# lock-shield.net
KiCad netlist of a schematic drawn in EAGLE
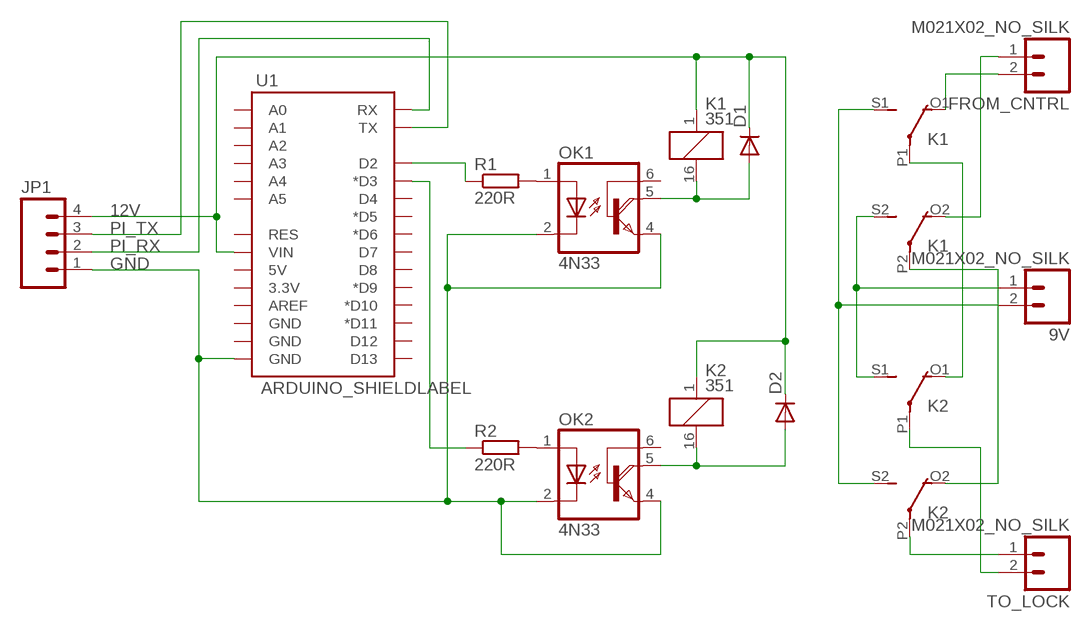
[diagram p0: schematic, sheet 1]

(export (version "E")
  (design (tool "Eeschema 10.0.6"))
  (components
    (comp (ref "9V")
      (value "M021X02_NO_SILK")
      (footprint "eagle-import:1X02_NO_SILK")
      (libsource (lib "eagle-import") (part "M021X02_NO_SILK"))
    )
    (comp (ref "D1")
      (value "DIODE1N4148")
      (footprint "eagle-import:DIODE-1N4148")
      (libsource (lib "eagle-import") (part "DIODE1N4148"))
    )
    (comp (ref "D2")
      (value "DIODE1N4148")
      (footprint "eagle-import:DIODE-1N4148")
      (libsource (lib "eagle-import") (part "DIODE1N4148"))
    )
    (comp (ref "FROM_CNTRL")
      (value "M021X02_NO_SILK")
      (footprint "eagle-import:1X02_NO_SILK")
      (libsource (lib "eagle-import") (part "M021X02_NO_SILK"))
    )
    (comp (ref "JP1")
      (value "M041X04_NO_SILK")
      (footprint "eagle-import:1X04_NO_SILK")
      (libsource (lib "eagle-import") (part "M041X04_NO_SILK"))
    )
    (comp (ref "K1")
      (value "351")
      (footprint "eagle-import:351")
      (libsource (lib "eagle-import") (part "351"))
    )
    (comp (ref "K2")
      (value "351")
      (footprint "eagle-import:351")
      (libsource (lib "eagle-import") (part "351"))
    )
    (comp (ref "OK1")
      (value "4N33")
      (footprint "eagle-import:DIL06")
      (fields (field (name "MF") "VISHAY/TELEFUNKEN"))
      (libsource (lib "eagle-import") (part "4N33"))
    )
    (comp (ref "OK2")
      (value "4N33")
      (footprint "eagle-import:DIL06")
      (fields (field (name "MF") "VISHAY/TELEFUNKEN"))
      (libsource (lib "eagle-import") (part "4N33"))
    )
    (comp (ref "R1")
      (value "220R")
      (footprint "eagle-import:0309_10")
      (libsource (lib "eagle-import") (part "R-EU_0309/10"))
    )
    (comp (ref "R2")
      (value "220R")
      (footprint "eagle-import:0309_10")
      (libsource (lib "eagle-import") (part "R-EU_0309/10"))
    )
    (comp (ref "TO_LOCK")
      (value "M021X02_NO_SILK")
      (footprint "eagle-import:1X02_NO_SILK")
      (libsource (lib "eagle-import") (part "M021X02_NO_SILK"))
    )
    (comp (ref "U1")
      (value "ARDUINO_SHIELDLABEL")
      (footprint "eagle-import:DUEMILANOVE_SHIELD")
      (libsource (lib "eagle-import") (part "ARDUINO_SHIELDLABEL"))
    )
  )
  (nets
    (net (code "1") (name "/12V") (class "Default")
      (node (ref "D1") (pin "C") (pinfunction "C_C") (pintype "passive"))
      (node (ref "D2") (pin "C") (pinfunction "C_C") (pintype "passive"))
      (node (ref "JP1") (pin "4") (pinfunction "4_4") (pintype "passive"))
      (node (ref "K1") (pin "1") (pinfunction "1_1") (pintype "passive"))
      (node (ref "K2") (pin "1") (pinfunction "1_1") (pintype "passive"))
      (node (ref "U1") (pin "VIN") (pinfunction "VIN_VIN") (pintype "bidirectional"))
    )
    (net (code "2") (name "/GND") (class "Default")
      (node (ref "JP1") (pin "1") (pinfunction "1_1") (pintype "passive"))
      (node (ref "OK1") (pin "2") (pinfunction "C_2") (pintype "passive"))
      (node (ref "OK1") (pin "4") (pinfunction "E_4") (pintype "passive"))
      (node (ref "OK2") (pin "2") (pinfunction "C_2") (pintype "passive"))
      (node (ref "OK2") (pin "4") (pinfunction "E_4") (pintype "passive"))
      (node (ref "U1") (pin "GND@0") (pinfunction "GND_GND@0") (pintype "bidirectional"))
    )
    (net (code "3") (name "/PI_RX") (class "Default")
      (node (ref "JP1") (pin "2") (pinfunction "2_2") (pintype "passive"))
      (node (ref "U1") (pin "RX") (pinfunction "RX_RX") (pintype "bidirectional"))
    )
    (net (code "4") (name "/PI_TX") (class "Default")
      (node (ref "JP1") (pin "3") (pinfunction "3_3") (pintype "passive"))
      (node (ref "U1") (pin "TX") (pinfunction "TX_TX") (pintype "bidirectional"))
    )
    (net (code "5") (name "Net-(K1A-2)") (class "Default")
      (node (ref "D1") (pin "A") (pinfunction "A_A") (pintype "passive"))
      (node (ref "K1") (pin "16") (pinfunction "2_16") (pintype "passive"))
      (node (ref "OK1") (pin "5") (pinfunction "COL_5") (pintype "passive"))
    )
    (net (code "6") (name "Net-(K1B-O)") (class "Default")
      (node (ref "FROM_CNTRL") (pin "2") (pinfunction "2_2") (pintype "passive"))
      (node (ref "K1") (pin "O1") (pinfunction "O_O1") (pintype "passive"))
    )
    (net (code "7") (name "Net-(K1B-P)") (class "Default")
      (node (ref "K1") (pin "P1") (pinfunction "P_P1") (pintype "passive"))
      (node (ref "K2") (pin "O1") (pinfunction "O_O1") (pintype "passive"))
    )
    (net (code "8") (name "Net-(K1B-S)") (class "Default")
      (node (ref "9V") (pin "2") (pinfunction "2_2") (pintype "passive"))
      (node (ref "K1") (pin "S1") (pinfunction "S_S1") (pintype "passive"))
      (node (ref "K2") (pin "S2") (pinfunction "S_S2") (pintype "passive"))
    )
    (net (code "9") (name "Net-(K1C-O)") (class "Default")
      (node (ref "FROM_CNTRL") (pin "1") (pinfunction "1_1") (pintype "passive"))
      (node (ref "K1") (pin "O2") (pinfunction "O_O2") (pintype "passive"))
    )
    (net (code "10") (name "Net-(K1C-P)") (class "Default")
      (node (ref "K1") (pin "P2") (pinfunction "P_P2") (pintype "passive"))
      (node (ref "K2") (pin "O2") (pinfunction "O_O2") (pintype "passive"))
    )
    (net (code "11") (name "Net-(K1C-S)") (class "Default")
      (node (ref "9V") (pin "1") (pinfunction "1_1") (pintype "passive"))
      (node (ref "K1") (pin "S2") (pinfunction "S_S2") (pintype "passive"))
      (node (ref "K2") (pin "S1") (pinfunction "S_S1") (pintype "passive"))
    )
    (net (code "12") (name "Net-(K2A-2)") (class "Default")
      (node (ref "D2") (pin "A") (pinfunction "A_A") (pintype "passive"))
      (node (ref "K2") (pin "16") (pinfunction "2_16") (pintype "passive"))
      (node (ref "OK2") (pin "5") (pinfunction "COL_5") (pintype "passive"))
    )
    (net (code "13") (name "Net-(K2B-P)") (class "Default")
      (node (ref "K2") (pin "P1") (pinfunction "P_P1") (pintype "passive"))
      (node (ref "TO_LOCK") (pin "2") (pinfunction "2_2") (pintype "passive"))
    )
    (net (code "14") (name "Net-(K2C-P)") (class "Default")
      (node (ref "K2") (pin "P2") (pinfunction "P_P2") (pintype "passive"))
      (node (ref "TO_LOCK") (pin "1") (pinfunction "1_1") (pintype "passive"))
    )
    (net (code "15") (name "Net-(OK1-A)") (class "Default")
      (node (ref "OK1") (pin "1") (pinfunction "A_1") (pintype "passive"))
      (node (ref "R1") (pin "2") (pinfunction "2_2") (pintype "passive"))
    )
    (net (code "16") (name "Net-(OK2-A)") (class "Default")
      (node (ref "OK2") (pin "1") (pinfunction "A_1") (pintype "passive"))
      (node (ref "R2") (pin "2") (pinfunction "2_2") (pintype "passive"))
    )
    (net (code "17") (name "Net-(R1-Pad1)") (class "Default")
      (node (ref "R1") (pin "1") (pinfunction "1_1") (pintype "passive"))
      (node (ref "U1") (pin "D2") (pinfunction "D2_D2") (pintype "bidirectional"))
    )
    (net (code "18") (name "Net-(U1-*D3)") (class "Default")
      (node (ref "R2") (pin "1") (pinfunction "1_1") (pintype "passive"))
      (node (ref "U1") (pin "D3") (pinfunction "*D3_D3") (pintype "bidirectional"))
    )
    (net (code "19") (name "unconnected-(OK1-B-Pad6)") (class "Default")
      (node (ref "OK1") (pin "6") (pinfunction "B_6") (pintype "passive"))
    )
    (net (code "20") (name "unconnected-(OK2-B-Pad6)") (class "Default")
      (node (ref "OK2") (pin "6") (pinfunction "B_6") (pintype "passive"))
    )
    (net (code "21") (name "unconnected-(U1-*D5-PadD5)") (class "Default")
      (node (ref "U1") (pin "D5") (pinfunction "*D5_D5") (pintype "bidirectional"))
    )
    (net (code "22") (name "unconnected-(U1-*D6-PadD6)") (class "Default")
      (node (ref "U1") (pin "D6") (pinfunction "*D6_D6") (pintype "bidirectional"))
    )
    (net (code "23") (name "unconnected-(U1-*D9-PadD9)") (class "Default")
      (node (ref "U1") (pin "D9") (pinfunction "*D9_D9") (pintype "bidirectional"))
    )
    (net (code "24") (name "unconnected-(U1-*D10-PadD10)") (class "Default")
      (node (ref "U1") (pin "D10") (pinfunction "*D10_D10") (pintype "bidirectional"))
    )
    (net (code "25") (name "unconnected-(U1-*D11-PadD11)") (class "Default")
      (node (ref "U1") (pin "D11") (pinfunction "*D11_D11") (pintype "bidirectional"))
    )
    (net (code "26") (name "unconnected-(U1-GND-PadGND@1)") (class "Default")
      (node (ref "U1") (pin "GND@1") (pinfunction "GND_GND@1") (pintype "bidirectional"))
    )
    (net (code "27") (name "unconnected-(U1-GND-PadGND@2)") (class "Default")
      (node (ref "U1") (pin "GND@2") (pinfunction "GND_GND@2") (pintype "bidirectional"))
    )
    (net (code "28") (name "unconnected-(U1-Pad3.3V)") (class "Default")
      (node (ref "U1") (pin "3.3V") (pinfunction "3.3V_3.3V") (pintype "bidirectional"))
    )
    (net (code "29") (name "unconnected-(U1-Pad5V)") (class "Default")
      (node (ref "U1") (pin "5V") (pinfunction "5V_5V") (pintype "bidirectional"))
    )
    (net (code "30") (name "unconnected-(U1-PadA0)") (class "Default")
      (node (ref "U1") (pin "A0") (pinfunction "A0_A0") (pintype "bidirectional"))
    )
    (net (code "31") (name "unconnected-(U1-PadA1)") (class "Default")
      (node (ref "U1") (pin "A1") (pinfunction "A1_A1") (pintype "bidirectional"))
    )
    (net (code "32") (name "unconnected-(U1-PadA2)") (class "Default")
      (node (ref "U1") (pin "A2") (pinfunction "A2_A2") (pintype "bidirectional"))
    )
    (net (code "33") (name "unconnected-(U1-PadA3)") (class "Default")
      (node (ref "U1") (pin "A3") (pinfunction "A3_A3") (pintype "bidirectional"))
    )
    (net (code "34") (name "unconnected-(U1-PadA4)") (class "Default")
      (node (ref "U1") (pin "A4") (pinfunction "A4_A4") (pintype "bidirectional"))
    )
    (net (code "35") (name "unconnected-(U1-PadA5)") (class "Default")
      (node (ref "U1") (pin "A5") (pinfunction "A5_A5") (pintype "bidirectional"))
    )
    (net (code "36") (name "unconnected-(U1-PadAREF)") (class "Default")
      (node (ref "U1") (pin "AREF") (pinfunction "AREF_AREF") (pintype "bidirectional"))
    )
    (net (code "37") (name "unconnected-(U1-PadD4)") (class "Default")
      (node (ref "U1") (pin "D4") (pinfunction "D4_D4") (pintype "bidirectional"))
    )
    (net (code "38") (name "unconnected-(U1-PadD7)") (class "Default")
      (node (ref "U1") (pin "D7") (pinfunction "D7_D7") (pintype "bidirectional"))
    )
    (net (code "39") (name "unconnected-(U1-PadD8)") (class "Default")
      (node (ref "U1") (pin "D8") (pinfunction "D8_D8") (pintype "bidirectional"))
    )
    (net (code "40") (name "unconnected-(U1-PadD12)") (class "Default")
      (node (ref "U1") (pin "D12") (pinfunction "D12_D12") (pintype "bidirectional"))
    )
    (net (code "41") (name "unconnected-(U1-PadD13)") (class "Default")
      (node (ref "U1") (pin "D13") (pinfunction "D13_D13") (pintype "bidirectional"))
    )
    (net (code "42") (name "unconnected-(U1-PadRES)") (class "Default")
      (node (ref "U1") (pin "RES") (pinfunction "RES_RES") (pintype "bidirectional"))
    )
  )
)
